# untitled.net
KiCad netlist of a schematic drawn in EAGLE
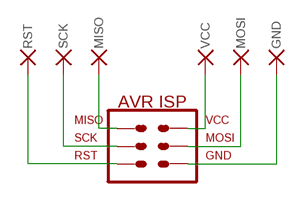
[diagram p0: schematic, sheet 1]

(export (version "E")
  (design (tool "Eeschema 10.0.6"))
  (components
    (comp (ref "GND")
      (value "GND")
      (footprint "eagle-import:POGO_PIN_P75-XX_HORIZONTALLY")
      (libsource (lib "eagle-import") (part "POGO_PIN_P75-XX_HORIZONTALLY"))
    )
    (comp (ref "MISO")
      (value "MISO")
      (footprint "eagle-import:POGO_PIN_P75-XX_HORIZONTALLY")
      (libsource (lib "eagle-import") (part "POGO_PIN_P75-XX_HORIZONTALLY"))
    )
    (comp (ref "MOSI")
      (value "MOSI")
      (footprint "eagle-import:POGO_PIN_P75-XX_HORIZONTALLY")
      (libsource (lib "eagle-import") (part "POGO_PIN_P75-XX_HORIZONTALLY"))
    )
    (comp (ref "RST")
      (value "RST")
      (footprint "eagle-import:POGO_PIN_P75-XX_HORIZONTALLY")
      (libsource (lib "eagle-import") (part "POGO_PIN_P75-XX_HORIZONTALLY"))
    )
    (comp (ref "SCK")
      (value "SCK")
      (footprint "eagle-import:POGO_PIN_P75-XX_HORIZONTALLY")
      (libsource (lib "eagle-import") (part "POGO_PIN_P75-XX_HORIZONTALLY"))
    )
    (comp (ref "VCC")
      (value "VCC")
      (footprint "eagle-import:POGO_PIN_P75-XX_HORIZONTALLY")
      (libsource (lib "eagle-import") (part "POGO_PIN_P75-XX_HORIZONTALLY"))
    )
    (comp (ref "X1")
      (value "AVR-ISP_10X_IDC_LOCK_EDGE_PCB")
      (footprint "eagle-import:AVR-ISP-10_EDGE_PCB")
      (libsource (lib "eagle-import") (part "AVR-ISP_10X_IDC_LOCK_EDGE_PCB"))
    )
  )
  (nets
    (net (code "1") (name "Net-(GND-P)") (class "Default")
      (node (ref "GND") (pin "P$1") (pinfunction "P_P$1") (pintype "passive"))
      (node (ref "X1") (pin "GND") (pinfunction "GND_GND") (pintype "passive"))
      (node (ref "X1") (pin "GND1") (pinfunction "GND_GND1") (pintype "passive"))
      (node (ref "X1") (pin "GND2") (pinfunction "GND_GND2") (pintype "passive"))
      (node (ref "X1") (pin "GND3") (pinfunction "GND_GND3") (pintype "passive"))
    )
    (net (code "2") (name "Net-(MISO-P)") (class "Default")
      (node (ref "MISO") (pin "P$1") (pinfunction "P_P$1") (pintype "passive"))
      (node (ref "X1") (pin "MISO") (pinfunction "MISO_MISO") (pintype "passive"))
    )
    (net (code "3") (name "Net-(MOSI-P)") (class "Default")
      (node (ref "MOSI") (pin "P$1") (pinfunction "P_P$1") (pintype "passive"))
      (node (ref "X1") (pin "MOSI") (pinfunction "MOSI_MOSI") (pintype "passive"))
    )
    (net (code "4") (name "Net-(RST-P)") (class "Default")
      (node (ref "RST") (pin "P$1") (pinfunction "P_P$1") (pintype "passive"))
      (node (ref "X1") (pin "RST") (pinfunction "RST_RST") (pintype "passive"))
    )
    (net (code "5") (name "Net-(SCK-P)") (class "Default")
      (node (ref "SCK") (pin "P$1") (pinfunction "P_P$1") (pintype "passive"))
      (node (ref "X1") (pin "SCK") (pinfunction "SCK_SCK") (pintype "passive"))
    )
    (net (code "6") (name "Net-(VCC-P)") (class "Default")
      (node (ref "VCC") (pin "P$1") (pinfunction "P_P$1") (pintype "passive"))
      (node (ref "X1") (pin "VCC") (pinfunction "VCC_VCC") (pintype "passive"))
    )
  )
)
